# ATMEGA168.net
KiCad netlist of a schematic drawn in EAGLE
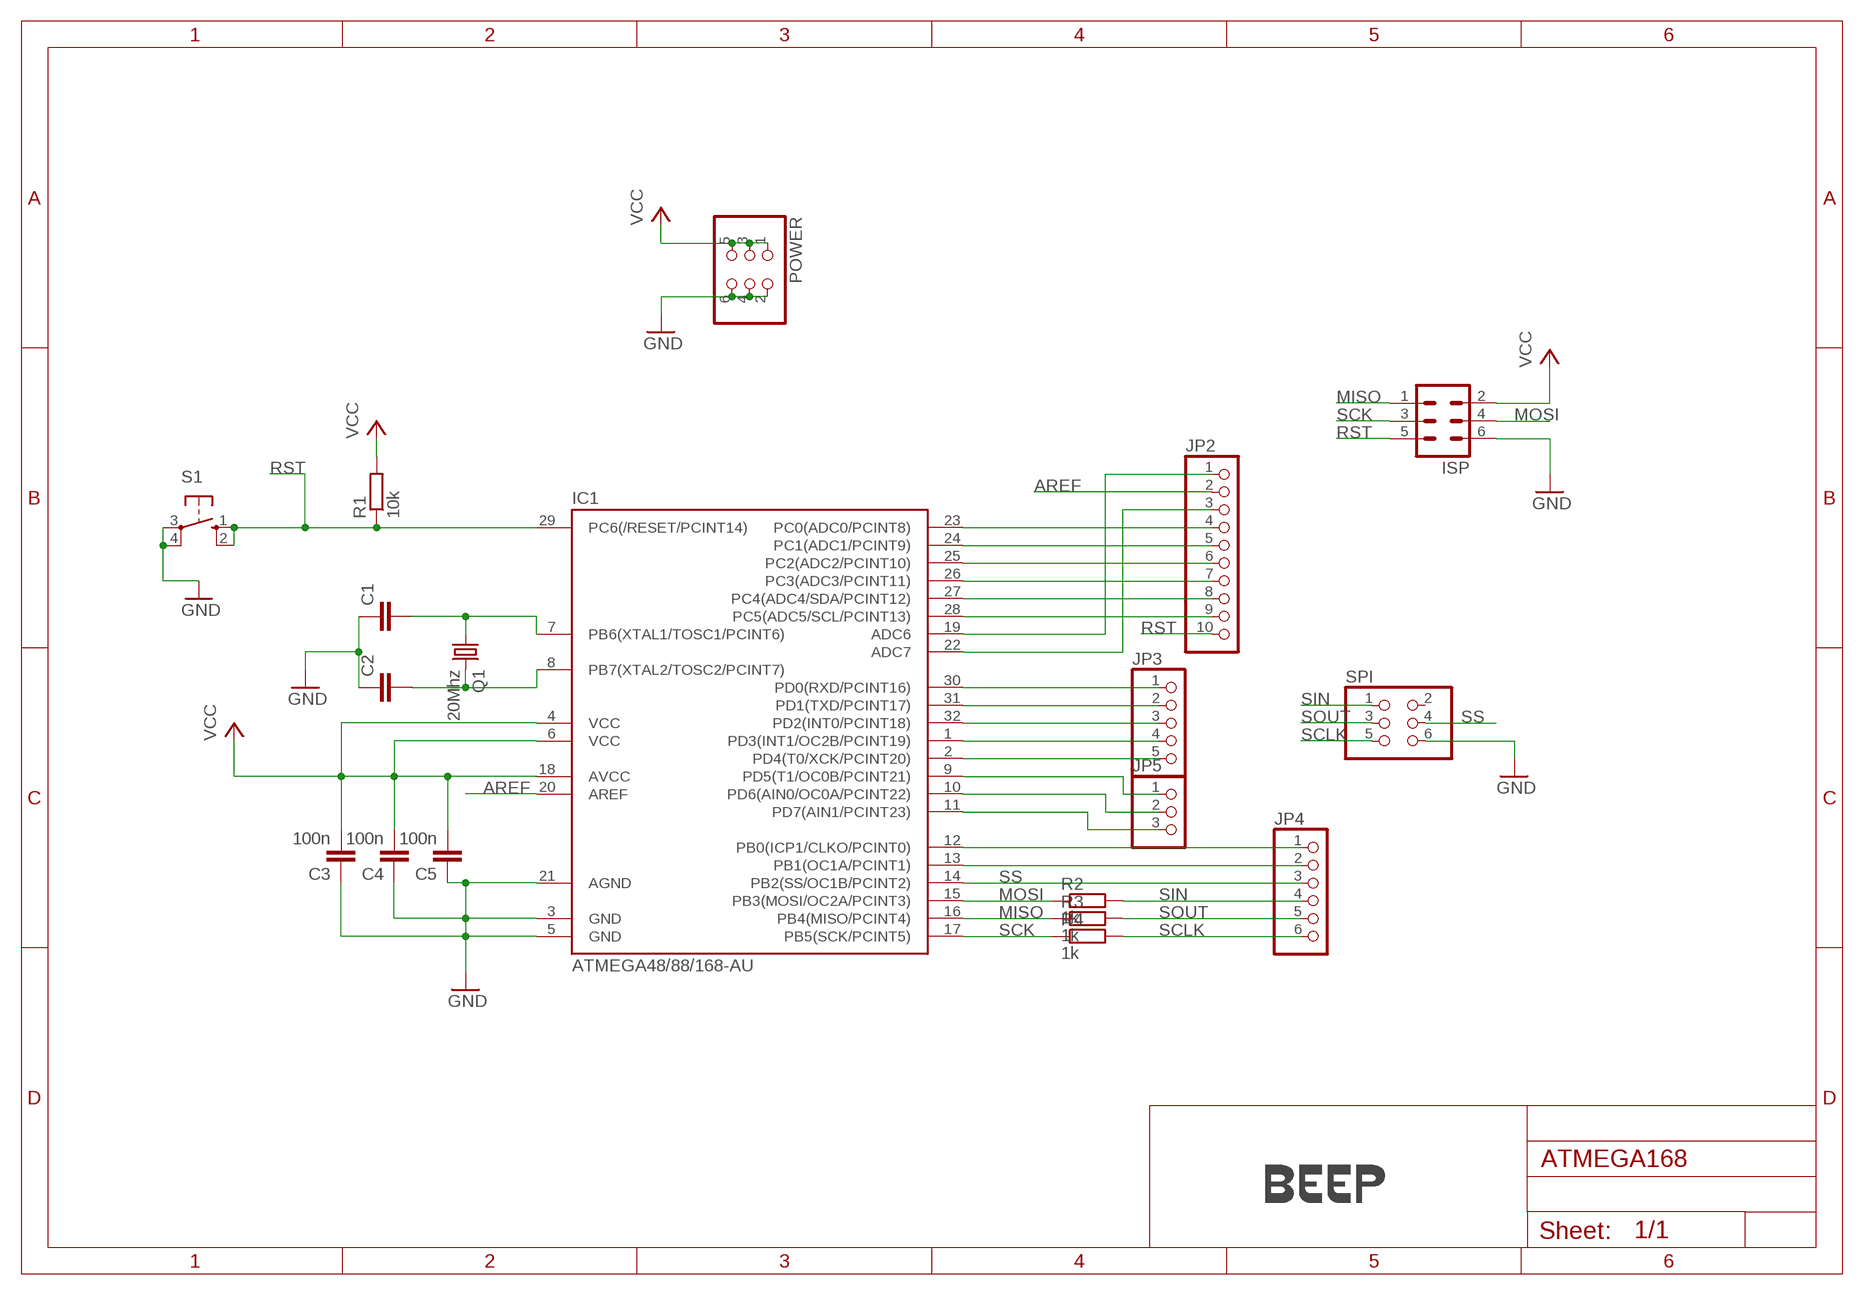
[diagram p0: schematic, sheet 1]

(export (version "E")
  (design (tool "Eeschema 10.0.6"))
  (components
    (comp (ref "C1")
      (value "C-EUC0805")
      (footprint "eagle-import:C0805")
      (libsource (lib "eagle-import") (part "C-EUC0805"))
    )
    (comp (ref "C2")
      (value "C-EUC0805")
      (footprint "eagle-import:C0805")
      (libsource (lib "eagle-import") (part "C-EUC0805"))
    )
    (comp (ref "C3")
      (value "100n")
      (footprint "eagle-import:C0805")
      (libsource (lib "eagle-import") (part "C-EUC0805"))
    )
    (comp (ref "C4")
      (value "100n")
      (footprint "eagle-import:C0805")
      (libsource (lib "eagle-import") (part "C-EUC0805"))
    )
    (comp (ref "C5")
      (value "100n")
      (footprint "eagle-import:C050-025X075")
      (libsource (lib "eagle-import") (part "C-EU050-025X075"))
    )
    (comp (ref "IC1")
      (value "ATMEGA48/88/168-AU")
      (footprint "eagle-import:TQFP32-08")
      (libsource (lib "eagle-import") (part "ATMEGA48/88/168-AU"))
    )
    (comp (ref "ISP")
      (value "ML6")
      (footprint "eagle-import:ML6")
      (libsource (lib "eagle-import") (part "ML6"))
    )
    (comp (ref "JP2")
      (value "PINHD-1X10")
      (footprint "eagle-import:1X10")
      (libsource (lib "eagle-import") (part "PINHD-1X10"))
    )
    (comp (ref "JP3")
      (value "PINHD-1X5")
      (footprint "eagle-import:1X05")
      (libsource (lib "eagle-import") (part "PINHD-1X5"))
    )
    (comp (ref "JP4")
      (value "PINHD-1X6")
      (footprint "eagle-import:1X06")
      (libsource (lib "eagle-import") (part "PINHD-1X6"))
    )
    (comp (ref "JP5")
      (value "PINHD-1X3")
      (footprint "eagle-import:1X03")
      (libsource (lib "eagle-import") (part "PINHD-1X3"))
    )
    (comp (ref "POWER")
      (value "PINHD-2X3")
      (footprint "eagle-import:2X03")
      (libsource (lib "eagle-import") (part "PINHD-2X3"))
    )
    (comp (ref "Q1")
      (value "20Mhz")
      (footprint "eagle-import:HC49_S")
      (libsource (lib "eagle-import") (part "CRYSTALHC49S"))
    )
    (comp (ref "R1")
      (value "10k")
      (footprint "eagle-import:M0805")
      (libsource (lib "eagle-import") (part "R-EU_M0805"))
    )
    (comp (ref "R2")
      (value "1k")
      (footprint "eagle-import:0207_7")
      (libsource (lib "eagle-import") (part "R-EU_0207/7"))
    )
    (comp (ref "R3")
      (value "1k")
      (footprint "eagle-import:0207_7")
      (libsource (lib "eagle-import") (part "R-EU_0207/7"))
    )
    (comp (ref "R4")
      (value "1k")
      (footprint "eagle-import:0207_7")
      (libsource (lib "eagle-import") (part "R-EU_0207/7"))
    )
    (comp (ref "S1")
      (value "10-XX")
      (footprint "eagle-import:B3F-10XX")
      (fields (field (name "MPN") "B3F-1000"))
      (libsource (lib "eagle-import") (part "10-XX"))
    )
    (comp (ref "SPI")
      (value "PINHD-2X3")
      (footprint "eagle-import:2X03")
      (libsource (lib "eagle-import") (part "PINHD-2X3"))
    )
    (comp (ref "U$1")
      (value "LOGO-COPPER4")
      (footprint "eagle-import:COPPER4")
      (libsource (lib "eagle-import") (part "LOGO-COPPER4"))
    )
  )
  (nets
    (net (code "1") (name "/AREF") (class "Default")
      (node (ref "IC1") (pin "20") (pinfunction "AREF_20") (pintype "passive"))
      (node (ref "JP2") (pin "2") (pinfunction "2_2") (pintype "passive"))
    )
    (net (code "2") (name "/MISO") (class "Default")
      (node (ref "IC1") (pin "16") (pinfunction "PB4(MISO/PCINT4)_16") (pintype "bidirectional"))
      (node (ref "ISP") (pin "1") (pinfunction "1_1") (pintype "passive"))
      (node (ref "R3") (pin "1") (pinfunction "1_1") (pintype "passive"))
    )
    (net (code "3") (name "/MOSI") (class "Default")
      (node (ref "IC1") (pin "15") (pinfunction "PB3(MOSI/OC2A/PCINT3)_15") (pintype "bidirectional"))
      (node (ref "ISP") (pin "4") (pinfunction "4_4") (pintype "passive"))
      (node (ref "R2") (pin "1") (pinfunction "1_1") (pintype "passive"))
    )
    (net (code "4") (name "/RST") (class "Default")
      (node (ref "IC1") (pin "29") (pinfunction "PC6(/RESET/PCINT14)_29") (pintype "bidirectional"))
      (node (ref "ISP") (pin "5") (pinfunction "5_5") (pintype "passive"))
      (node (ref "JP2") (pin "10") (pinfunction "10_10") (pintype "passive"))
      (node (ref "R1") (pin "1") (pinfunction "1_1") (pintype "passive"))
      (node (ref "S1") (pin "1") (pinfunction "S_1") (pintype "passive"))
      (node (ref "S1") (pin "2") (pinfunction "S1_2") (pintype "passive"))
    )
    (net (code "5") (name "/SCK") (class "Default")
      (node (ref "IC1") (pin "17") (pinfunction "PB5(SCK/PCINT5)_17") (pintype "bidirectional"))
      (node (ref "ISP") (pin "3") (pinfunction "3_3") (pintype "passive"))
      (node (ref "R4") (pin "1") (pinfunction "1_1") (pintype "passive"))
    )
    (net (code "6") (name "/SCLK") (class "Default")
      (node (ref "JP4") (pin "6") (pinfunction "6_6") (pintype "passive"))
      (node (ref "R4") (pin "2") (pinfunction "2_2") (pintype "passive"))
      (node (ref "SPI") (pin "5") (pinfunction "5_5") (pintype "passive"))
    )
    (net (code "7") (name "/SIN") (class "Default")
      (node (ref "JP4") (pin "4") (pinfunction "4_4") (pintype "passive"))
      (node (ref "R2") (pin "2") (pinfunction "2_2") (pintype "passive"))
      (node (ref "SPI") (pin "1") (pinfunction "1_1") (pintype "passive"))
    )
    (net (code "8") (name "/SOUT") (class "Default")
      (node (ref "JP4") (pin "5") (pinfunction "5_5") (pintype "passive"))
      (node (ref "R3") (pin "2") (pinfunction "2_2") (pintype "passive"))
      (node (ref "SPI") (pin "3") (pinfunction "3_3") (pintype "passive"))
    )
    (net (code "9") (name "/SS") (class "Default")
      (node (ref "IC1") (pin "14") (pinfunction "PB2(SS/OC1B/PCINT2)_14") (pintype "bidirectional"))
      (node (ref "JP4") (pin "3") (pinfunction "3_3") (pintype "passive"))
      (node (ref "SPI") (pin "4") (pinfunction "4_4") (pintype "passive"))
    )
    (net (code "10") (name "GND") (class "Default")
      (node (ref "C1") (pin "1") (pinfunction "1_1") (pintype "passive"))
      (node (ref "C2") (pin "1") (pinfunction "1_1") (pintype "passive"))
      (node (ref "C3") (pin "1") (pinfunction "1_1") (pintype "passive"))
      (node (ref "C4") (pin "1") (pinfunction "1_1") (pintype "passive"))
      (node (ref "C5") (pin "1") (pinfunction "1_1") (pintype "passive"))
      (node (ref "IC1") (pin "21") (pinfunction "AGND_21") (pintype "power_in"))
      (node (ref "IC1") (pin "3") (pinfunction "GND_3") (pintype "power_in"))
      (node (ref "IC1") (pin "5") (pinfunction "GND_5") (pintype "power_in"))
      (node (ref "ISP") (pin "6") (pinfunction "6_6") (pintype "passive"))
      (node (ref "POWER") (pin "2") (pinfunction "2_2") (pintype "passive"))
      (node (ref "POWER") (pin "4") (pinfunction "4_4") (pintype "passive"))
      (node (ref "POWER") (pin "6") (pinfunction "6_6") (pintype "passive"))
      (node (ref "S1") (pin "3") (pinfunction "P_3") (pintype "passive"))
      (node (ref "S1") (pin "4") (pinfunction "P1_4") (pintype "passive"))
      (node (ref "SPI") (pin "6") (pinfunction "6_6") (pintype "passive"))
    )
    (net (code "11") (name "Net-(IC1-ADC6)") (class "Default")
      (node (ref "IC1") (pin "19") (pinfunction "ADC6_19") (pintype "passive"))
      (node (ref "JP2") (pin "1") (pinfunction "1_1") (pintype "passive"))
    )
    (net (code "12") (name "Net-(IC1-ADC7)") (class "Default")
      (node (ref "IC1") (pin "22") (pinfunction "ADC7_22") (pintype "passive"))
      (node (ref "JP2") (pin "3") (pinfunction "3_3") (pintype "passive"))
    )
    (net (code "13") (name "Net-(IC1-PB0(ICP1{slash}CLKO{slash}PCINT0))") (class "Default")
      (node (ref "IC1") (pin "12") (pinfunction "PB0(ICP1/CLKO/PCINT0)_12") (pintype "bidirectional"))
      (node (ref "JP4") (pin "1") (pinfunction "1_1") (pintype "passive"))
    )
    (net (code "14") (name "Net-(IC1-PB1(OC1A{slash}PCINT1))") (class "Default")
      (node (ref "IC1") (pin "13") (pinfunction "PB1(OC1A/PCINT1)_13") (pintype "bidirectional"))
      (node (ref "JP4") (pin "2") (pinfunction "2_2") (pintype "passive"))
    )
    (net (code "15") (name "Net-(IC1-PB6(XTAL1{slash}TOSC1{slash}PCINT6))") (class "Default")
      (node (ref "C1") (pin "2") (pinfunction "2_2") (pintype "passive"))
      (node (ref "IC1") (pin "7") (pinfunction "PB6(XTAL1/TOSC1/PCINT6)_7") (pintype "bidirectional"))
      (node (ref "Q1") (pin "1") (pinfunction "1_1") (pintype "passive"))
    )
    (net (code "16") (name "Net-(IC1-PB7(XTAL2{slash}TOSC2{slash}PCINT7))") (class "Default")
      (node (ref "C2") (pin "2") (pinfunction "2_2") (pintype "passive"))
      (node (ref "IC1") (pin "8") (pinfunction "PB7(XTAL2/TOSC2/PCINT7)_8") (pintype "bidirectional"))
      (node (ref "Q1") (pin "2") (pinfunction "2_2") (pintype "passive"))
    )
    (net (code "17") (name "Net-(IC1-PC0(ADC0{slash}PCINT8))") (class "Default")
      (node (ref "IC1") (pin "23") (pinfunction "PC0(ADC0/PCINT8)_23") (pintype "bidirectional"))
      (node (ref "JP2") (pin "4") (pinfunction "4_4") (pintype "passive"))
    )
    (net (code "18") (name "Net-(IC1-PC1(ADC1{slash}PCINT9))") (class "Default")
      (node (ref "IC1") (pin "24") (pinfunction "PC1(ADC1/PCINT9)_24") (pintype "bidirectional"))
      (node (ref "JP2") (pin "5") (pinfunction "5_5") (pintype "passive"))
    )
    (net (code "19") (name "Net-(IC1-PC2(ADC2{slash}PCINT10))") (class "Default")
      (node (ref "IC1") (pin "25") (pinfunction "PC2(ADC2/PCINT10)_25") (pintype "bidirectional"))
      (node (ref "JP2") (pin "6") (pinfunction "6_6") (pintype "passive"))
    )
    (net (code "20") (name "Net-(IC1-PC3(ADC3{slash}PCINT11))") (class "Default")
      (node (ref "IC1") (pin "26") (pinfunction "PC3(ADC3/PCINT11)_26") (pintype "bidirectional"))
      (node (ref "JP2") (pin "7") (pinfunction "7_7") (pintype "passive"))
    )
    (net (code "21") (name "Net-(IC1-PC4(ADC4{slash}SDA{slash}PCINT12))") (class "Default")
      (node (ref "IC1") (pin "27") (pinfunction "PC4(ADC4/SDA/PCINT12)_27") (pintype "bidirectional"))
      (node (ref "JP2") (pin "8") (pinfunction "8_8") (pintype "passive"))
    )
    (net (code "22") (name "Net-(IC1-PC5(ADC5{slash}SCL{slash}PCINT13))") (class "Default")
      (node (ref "IC1") (pin "28") (pinfunction "PC5(ADC5/SCL/PCINT13)_28") (pintype "bidirectional"))
      (node (ref "JP2") (pin "9") (pinfunction "9_9") (pintype "passive"))
    )
    (net (code "23") (name "Net-(IC1-PD0(RXD{slash}PCINT16))") (class "Default")
      (node (ref "IC1") (pin "30") (pinfunction "PD0(RXD/PCINT16)_30") (pintype "bidirectional"))
      (node (ref "JP3") (pin "1") (pinfunction "1_1") (pintype "passive"))
    )
    (net (code "24") (name "Net-(IC1-PD1(TXD{slash}PCINT17))") (class "Default")
      (node (ref "IC1") (pin "31") (pinfunction "PD1(TXD/PCINT17)_31") (pintype "bidirectional"))
      (node (ref "JP3") (pin "2") (pinfunction "2_2") (pintype "passive"))
    )
    (net (code "25") (name "Net-(IC1-PD2(INT0{slash}PCINT18))") (class "Default")
      (node (ref "IC1") (pin "32") (pinfunction "PD2(INT0/PCINT18)_32") (pintype "bidirectional"))
      (node (ref "JP3") (pin "3") (pinfunction "3_3") (pintype "passive"))
    )
    (net (code "26") (name "Net-(IC1-PD3(INT1{slash}OC2B{slash}PCINT19))") (class "Default")
      (node (ref "IC1") (pin "1") (pinfunction "PD3(INT1/OC2B/PCINT19)_1") (pintype "bidirectional"))
      (node (ref "JP3") (pin "4") (pinfunction "4_4") (pintype "passive"))
    )
    (net (code "27") (name "Net-(IC1-PD4(T0{slash}XCK{slash}PCINT20))") (class "Default")
      (node (ref "IC1") (pin "2") (pinfunction "PD4(T0/XCK/PCINT20)_2") (pintype "bidirectional"))
      (node (ref "JP3") (pin "5") (pinfunction "5_5") (pintype "passive"))
    )
    (net (code "28") (name "Net-(IC1-PD5(T1{slash}OC0B{slash}PCINT21))") (class "Default")
      (node (ref "IC1") (pin "9") (pinfunction "PD5(T1/OC0B/PCINT21)_9") (pintype "bidirectional"))
      (node (ref "JP5") (pin "1") (pinfunction "1_1") (pintype "passive"))
    )
    (net (code "29") (name "Net-(IC1-PD6(AIN0{slash}OC0A{slash}PCINT22))") (class "Default")
      (node (ref "IC1") (pin "10") (pinfunction "PD6(AIN0/OC0A/PCINT22)_10") (pintype "bidirectional"))
      (node (ref "JP5") (pin "2") (pinfunction "2_2") (pintype "passive"))
    )
    (net (code "30") (name "Net-(IC1-PD7(AIN1{slash}PCINT23))") (class "Default")
      (node (ref "IC1") (pin "11") (pinfunction "PD7(AIN1/PCINT23)_11") (pintype "bidirectional"))
      (node (ref "JP5") (pin "3") (pinfunction "3_3") (pintype "passive"))
    )
    (net (code "31") (name "VCC") (class "Default")
      (node (ref "C3") (pin "2") (pinfunction "2_2") (pintype "passive"))
      (node (ref "C4") (pin "2") (pinfunction "2_2") (pintype "passive"))
      (node (ref "C5") (pin "2") (pinfunction "2_2") (pintype "passive"))
      (node (ref "IC1") (pin "18") (pinfunction "AVCC_18") (pintype "passive"))
      (node (ref "IC1") (pin "4") (pinfunction "VCC_4") (pintype "power_in"))
      (node (ref "IC1") (pin "6") (pinfunction "VCC_6") (pintype "power_in"))
      (node (ref "ISP") (pin "2") (pinfunction "2_2") (pintype "passive"))
      (node (ref "POWER") (pin "1") (pinfunction "1_1") (pintype "passive"))
      (node (ref "POWER") (pin "3") (pinfunction "3_3") (pintype "passive"))
      (node (ref "POWER") (pin "5") (pinfunction "5_5") (pintype "passive"))
      (node (ref "R1") (pin "2") (pinfunction "2_2") (pintype "passive"))
    )
    (net (code "32") (name "unconnected-(SPI-Pad2)") (class "Default")
      (node (ref "SPI") (pin "2") (pinfunction "2_2") (pintype "passive"))
    )
  )
)
